# DigiSporc.net
KiCad netlist of a schematic drawn in EAGLE
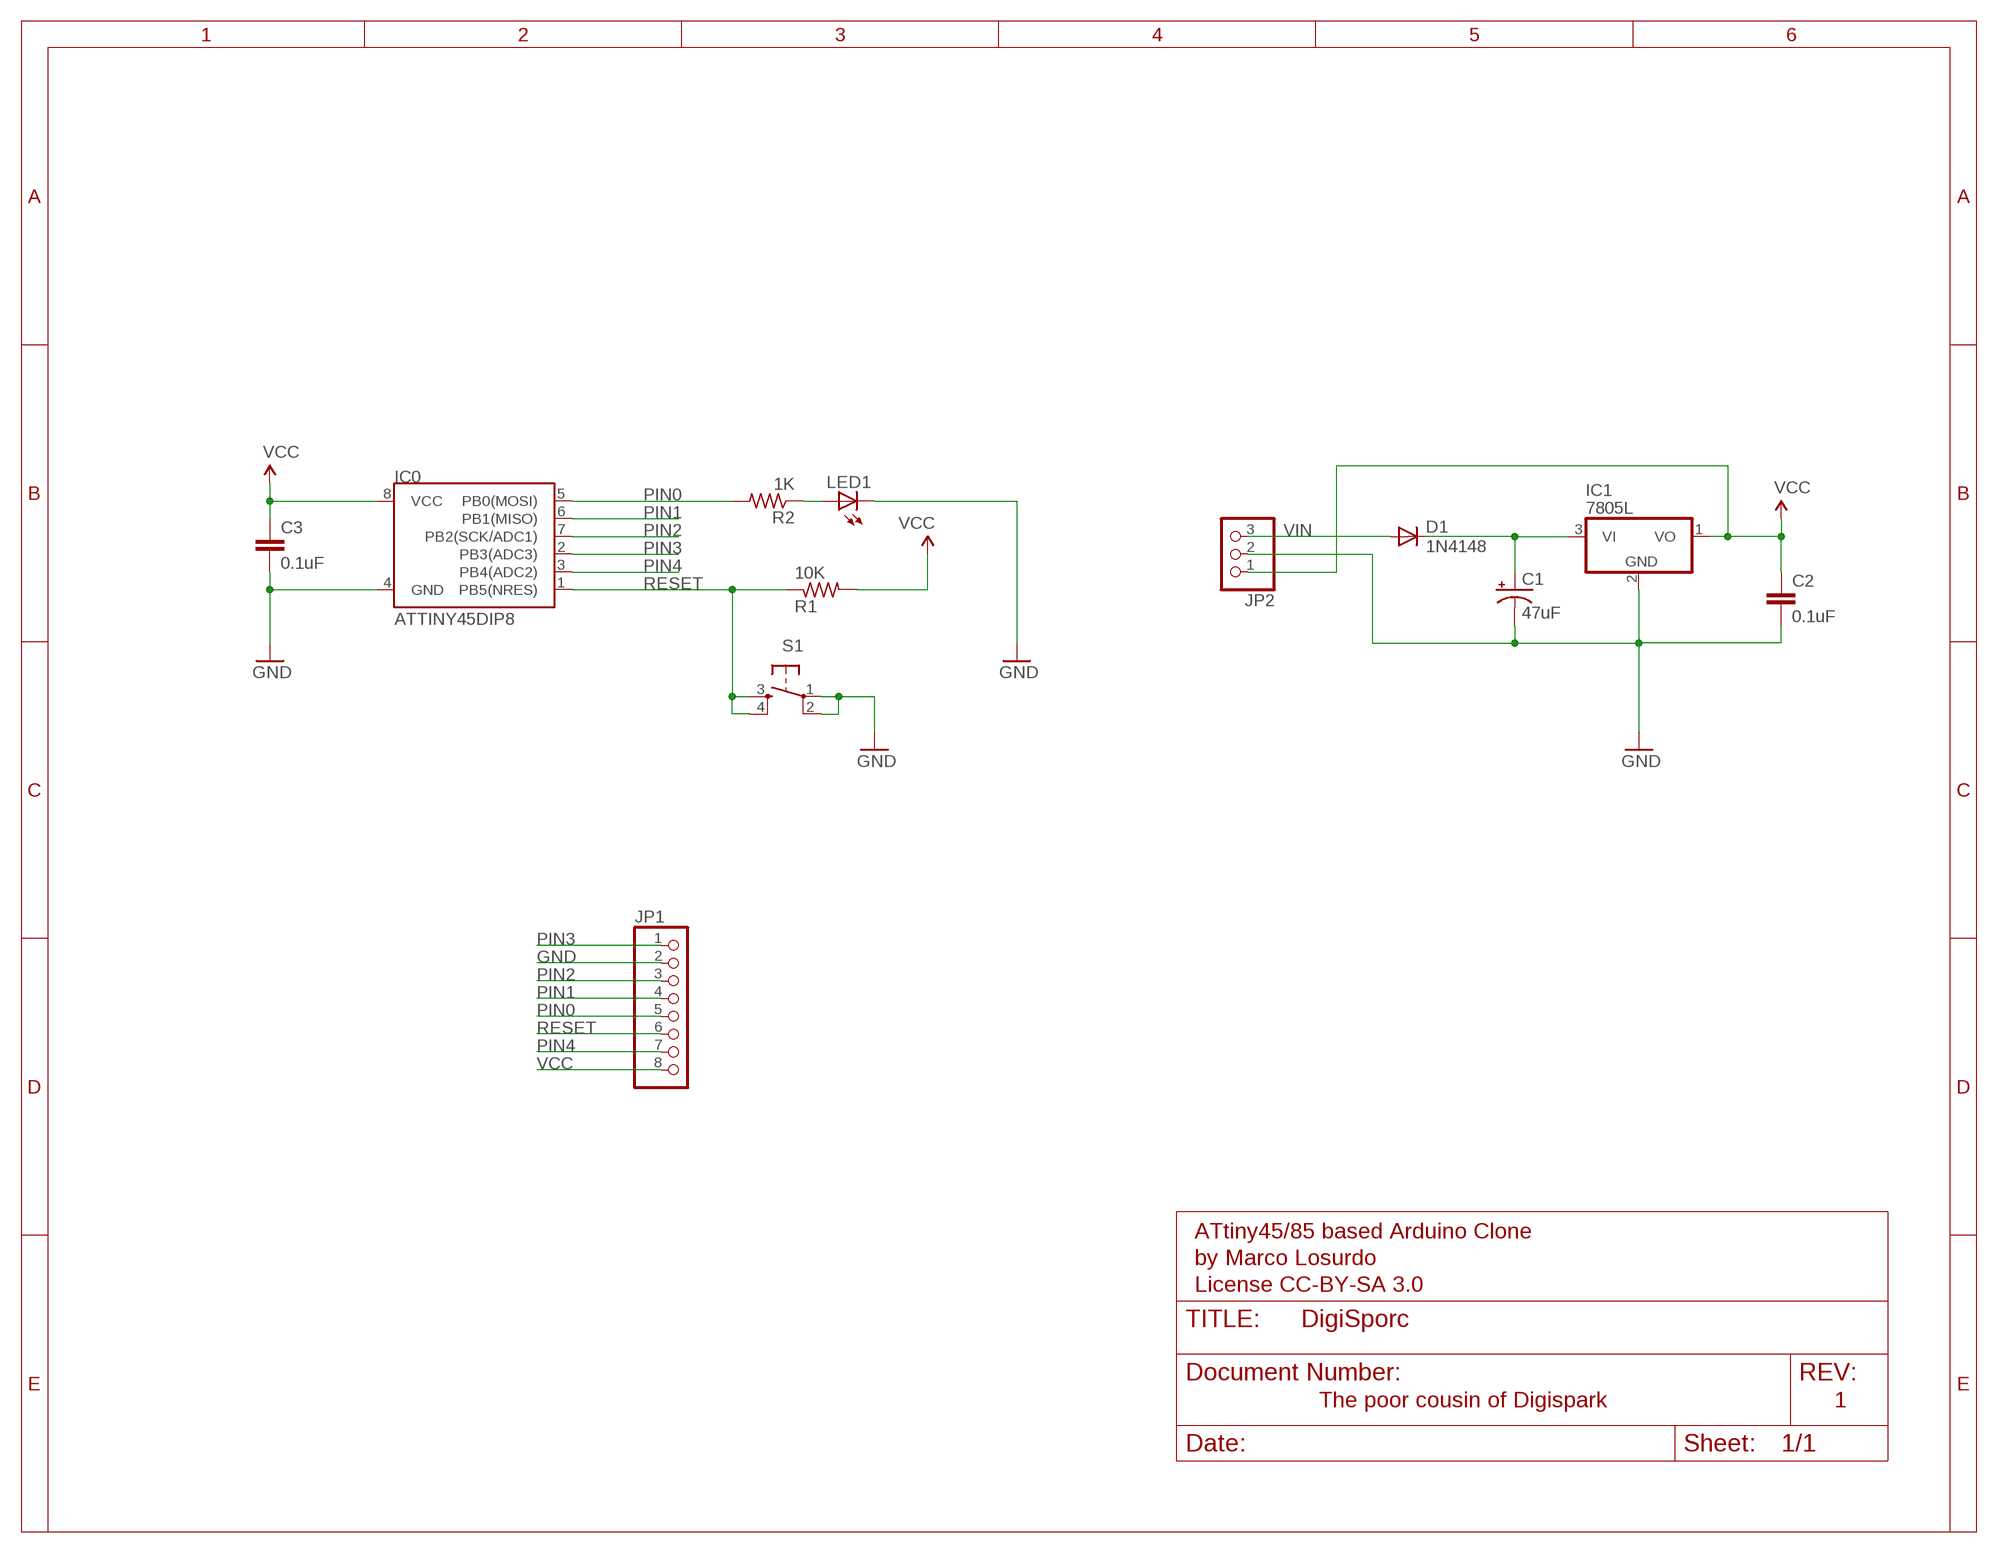
[diagram p0: schematic, sheet 1]

(export (version "E")
  (design (tool "Eeschema 10.0.6"))
  (components
    (comp (ref "C1")
      (value "47uF")
      (footprint "eagle-import:E2-5")
      (libsource (lib "eagle-import") (part "CPOL-USE2-5"))
    )
    (comp (ref "C2")
      (value "0.1uF")
      (footprint "eagle-import:CAP-PTH-SMALL")
      (libsource (lib "eagle-import") (part "CAPPTH"))
    )
    (comp (ref "C3")
      (value "0.1uF")
      (footprint "eagle-import:CAP-PTH-SMALL")
      (libsource (lib "eagle-import") (part "CAPPTH"))
    )
    (comp (ref "D1")
      (value "1N4148")
      (footprint "eagle-import:D-5")
      (libsource (lib "eagle-import") (part "DIODE-D-5"))
    )
    (comp (ref "IC0")
      (value "ATTINY45DIP8")
      (footprint "eagle-import:DIP08")
      (libsource (lib "eagle-import") (part "ATTINY45DIP8"))
    )
    (comp (ref "IC1")
      (value "7805L")
      (footprint "eagle-import:TO92")
      (libsource (lib "eagle-import") (part "78L05"))
    )
    (comp (ref "JP1")
      (value "PINHD-1X8")
      (footprint "eagle-import:1X08")
      (libsource (lib "eagle-import") (part "PINHD-1X8"))
    )
    (comp (ref "JP2")
      (value "PINHD-1X3")
      (footprint "eagle-import:1X03")
      (libsource (lib "eagle-import") (part "PINHD-1X3"))
    )
    (comp (ref "LED1")
      (value "LED3MM")
      (footprint "eagle-import:LED3MM")
      (libsource (lib "eagle-import") (part "LED3MM"))
    )
    (comp (ref "R1")
      (value "10K")
      (footprint "eagle-import:0204_7")
      (libsource (lib "eagle-import") (part "R-US_0204/7"))
    )
    (comp (ref "R2")
      (value "1K")
      (footprint "eagle-import:0204_7")
      (libsource (lib "eagle-import") (part "R-US_0204/7"))
    )
    (comp (ref "S1")
      (value "TAC_SWITCHPTH")
      (footprint "eagle-import:TACTILE-PTH")
      (libsource (lib "eagle-import") (part "TAC_SWITCHPTH"))
    )
  )
  (nets
    (net (code "1") (name "/PIN0") (class "Default")
      (node (ref "IC0") (pin "5") (pinfunction "PB0(MOSI)_5") (pintype "bidirectional"))
      (node (ref "JP1") (pin "5") (pinfunction "5_5") (pintype "passive"))
      (node (ref "R2") (pin "2") (pinfunction "2_2") (pintype "passive"))
    )
    (net (code "2") (name "/PIN1") (class "Default")
      (node (ref "IC0") (pin "6") (pinfunction "PB1(MISO)_6") (pintype "bidirectional"))
      (node (ref "JP1") (pin "4") (pinfunction "4_4") (pintype "passive"))
    )
    (net (code "3") (name "/PIN2") (class "Default")
      (node (ref "IC0") (pin "7") (pinfunction "PB2(SCK/ADC1)_7") (pintype "bidirectional"))
      (node (ref "JP1") (pin "3") (pinfunction "3_3") (pintype "passive"))
    )
    (net (code "4") (name "/PIN3") (class "Default")
      (node (ref "IC0") (pin "2") (pinfunction "PB3(ADC3)_2") (pintype "bidirectional"))
      (node (ref "JP1") (pin "1") (pinfunction "1_1") (pintype "passive"))
    )
    (net (code "5") (name "/PIN4") (class "Default")
      (node (ref "IC0") (pin "3") (pinfunction "PB4(ADC2)_3") (pintype "bidirectional"))
      (node (ref "JP1") (pin "7") (pinfunction "7_7") (pintype "passive"))
    )
    (net (code "6") (name "/RESET") (class "Default")
      (node (ref "IC0") (pin "1") (pinfunction "PB5(NRES)_1") (pintype "bidirectional"))
      (node (ref "JP1") (pin "6") (pinfunction "6_6") (pintype "passive"))
      (node (ref "R1") (pin "1") (pinfunction "1_1") (pintype "passive"))
      (node (ref "S1") (pin "3") (pinfunction "3_3") (pintype "passive"))
      (node (ref "S1") (pin "4") (pinfunction "4_4") (pintype "passive"))
    )
    (net (code "7") (name "/VIN") (class "Default")
      (node (ref "D1") (pin "A") (pinfunction "A_A") (pintype "passive"))
      (node (ref "JP2") (pin "3") (pinfunction "3_3") (pintype "passive"))
    )
    (net (code "8") (name "GND") (class "Default")
      (node (ref "C1") (pin "-") (pinfunction "-_-") (pintype "passive"))
      (node (ref "C2") (pin "2") (pinfunction "2_2") (pintype "passive"))
      (node (ref "C3") (pin "2") (pinfunction "2_2") (pintype "passive"))
      (node (ref "IC0") (pin "4") (pinfunction "GND_4") (pintype "bidirectional"))
      (node (ref "IC1") (pin "2") (pinfunction "GND_2") (pintype "passive"))
      (node (ref "JP1") (pin "2") (pinfunction "2_2") (pintype "passive"))
      (node (ref "JP2") (pin "2") (pinfunction "2_2") (pintype "passive"))
      (node (ref "LED1") (pin "K") (pinfunction "C_K") (pintype "passive"))
      (node (ref "S1") (pin "1") (pinfunction "1_1") (pintype "passive"))
      (node (ref "S1") (pin "2") (pinfunction "2_2") (pintype "passive"))
    )
    (net (code "9") (name "Net-(IC1-VI)") (class "Default")
      (node (ref "C1") (pin "+") (pinfunction "+_+") (pintype "passive"))
      (node (ref "D1") (pin "C") (pinfunction "C_C") (pintype "passive"))
      (node (ref "IC1") (pin "3") (pinfunction "VI_3") (pintype "input"))
    )
    (net (code "10") (name "Net-(LED1-PadA)") (class "Default")
      (node (ref "LED1") (pin "A") (pinfunction "A_A") (pintype "passive"))
      (node (ref "R2") (pin "1") (pinfunction "1_1") (pintype "passive"))
    )
    (net (code "11") (name "VCC") (class "Default")
      (node (ref "C2") (pin "1") (pinfunction "1_1") (pintype "passive"))
      (node (ref "C3") (pin "1") (pinfunction "1_1") (pintype "passive"))
      (node (ref "IC0") (pin "8") (pinfunction "VCC_8") (pintype "bidirectional"))
      (node (ref "IC1") (pin "1") (pinfunction "VO_1") (pintype "passive"))
      (node (ref "JP1") (pin "8") (pinfunction "8_8") (pintype "passive"))
      (node (ref "JP2") (pin "1") (pinfunction "1_1") (pintype "passive"))
      (node (ref "R1") (pin "2") (pinfunction "2_2") (pintype "passive"))
    )
  )
)
